# Sheet1.net
KiCad netlist of a schematic drawn in Altium Designer
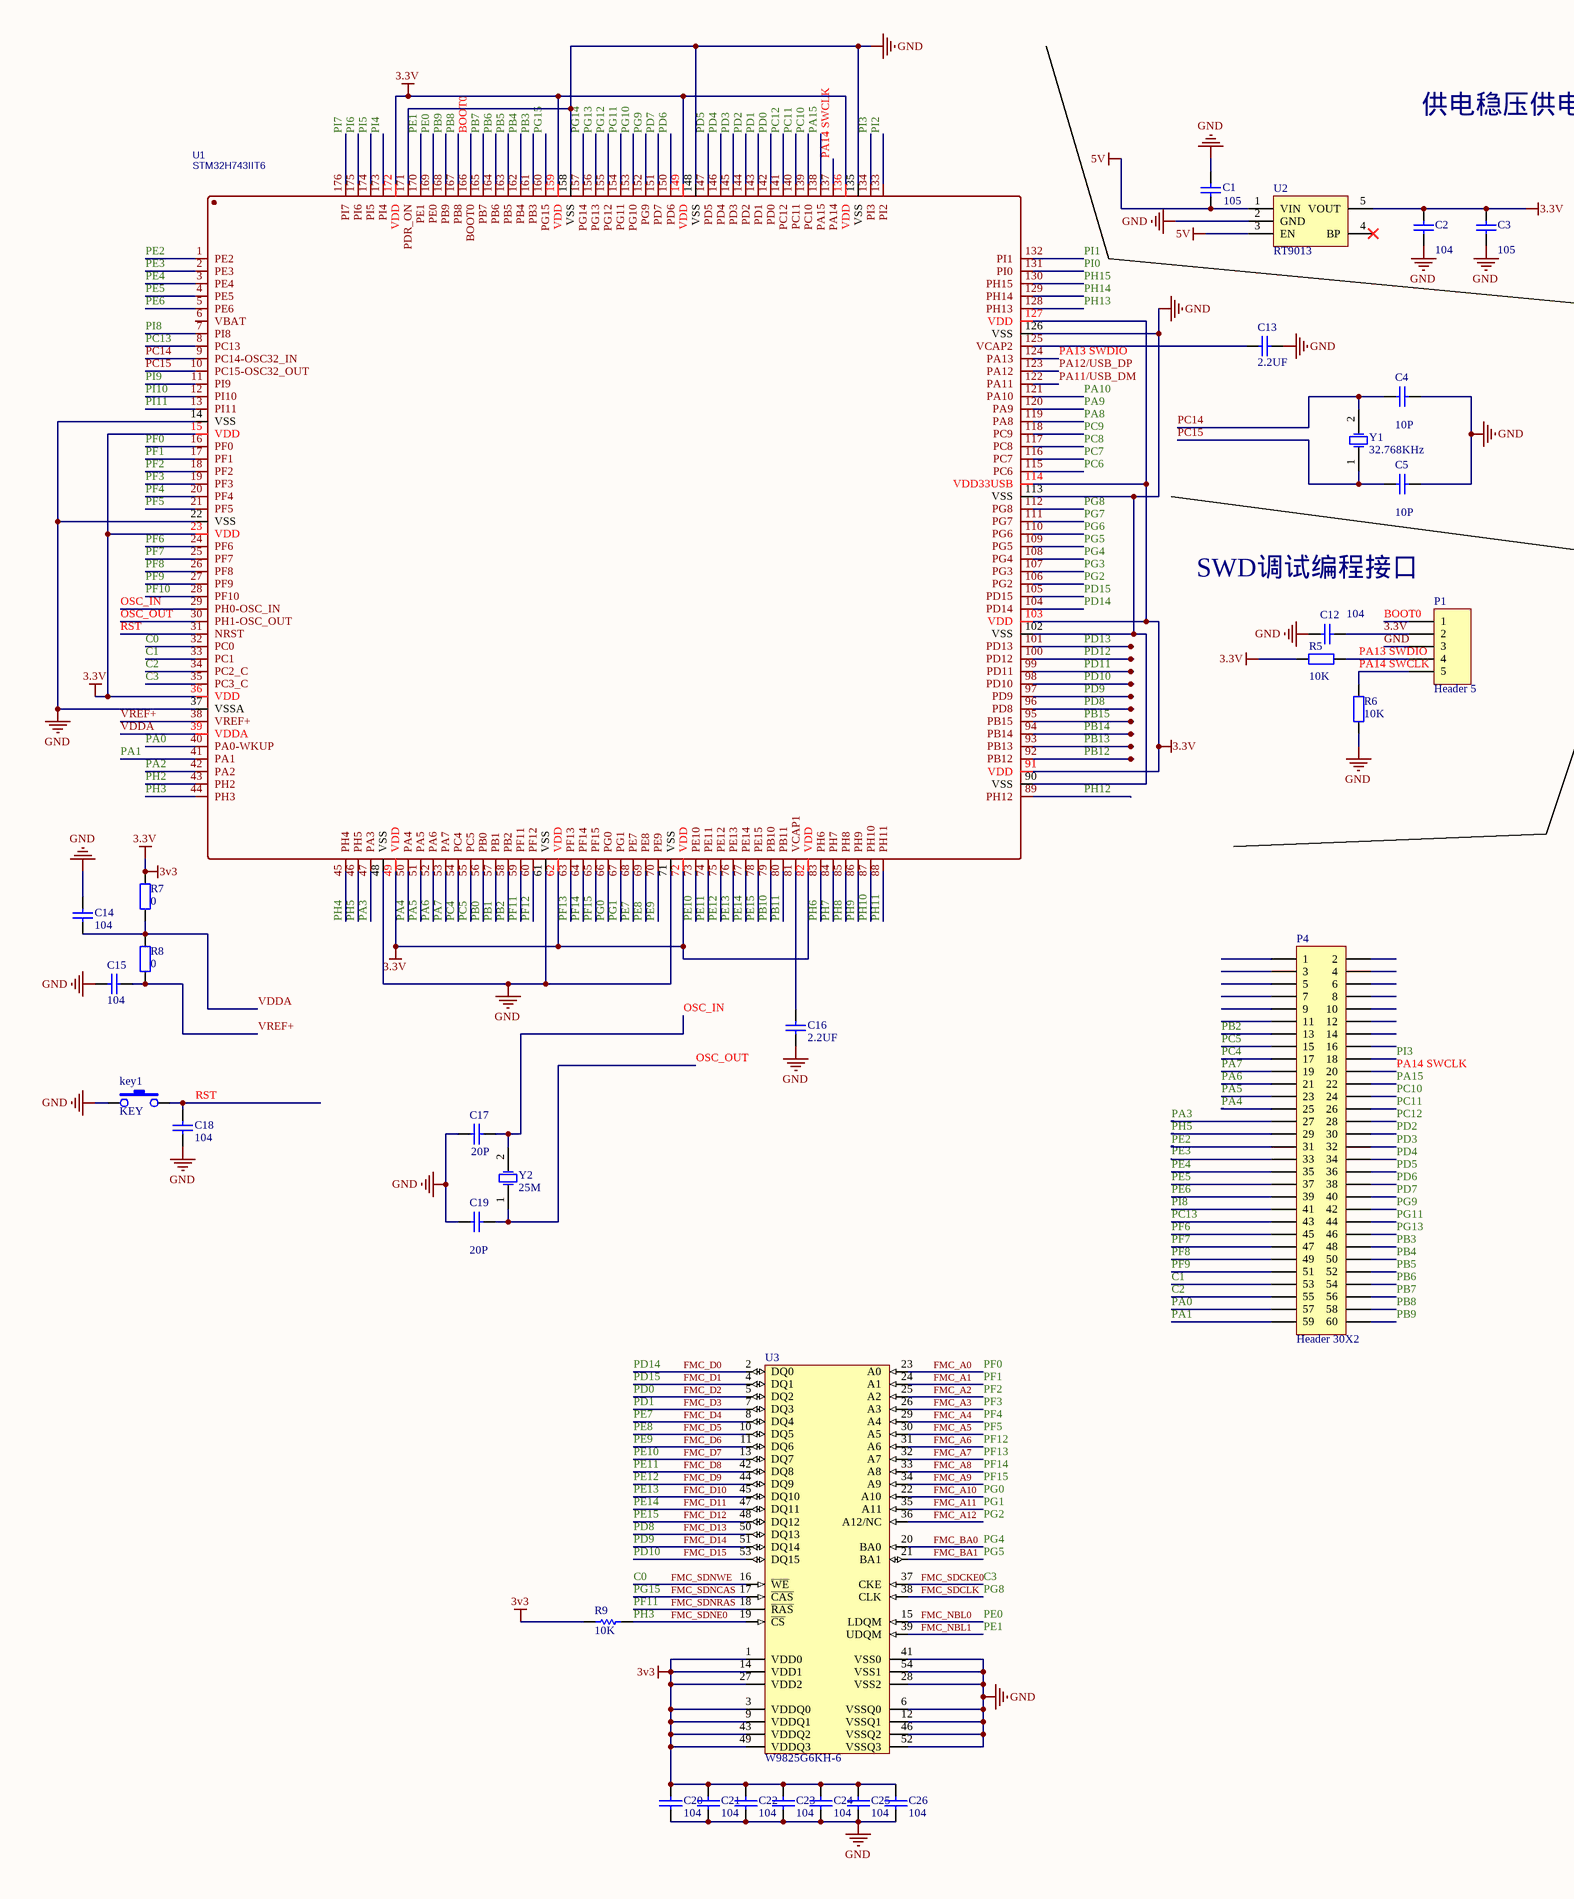
[diagram p0: Sheet1.SchDoc, left]
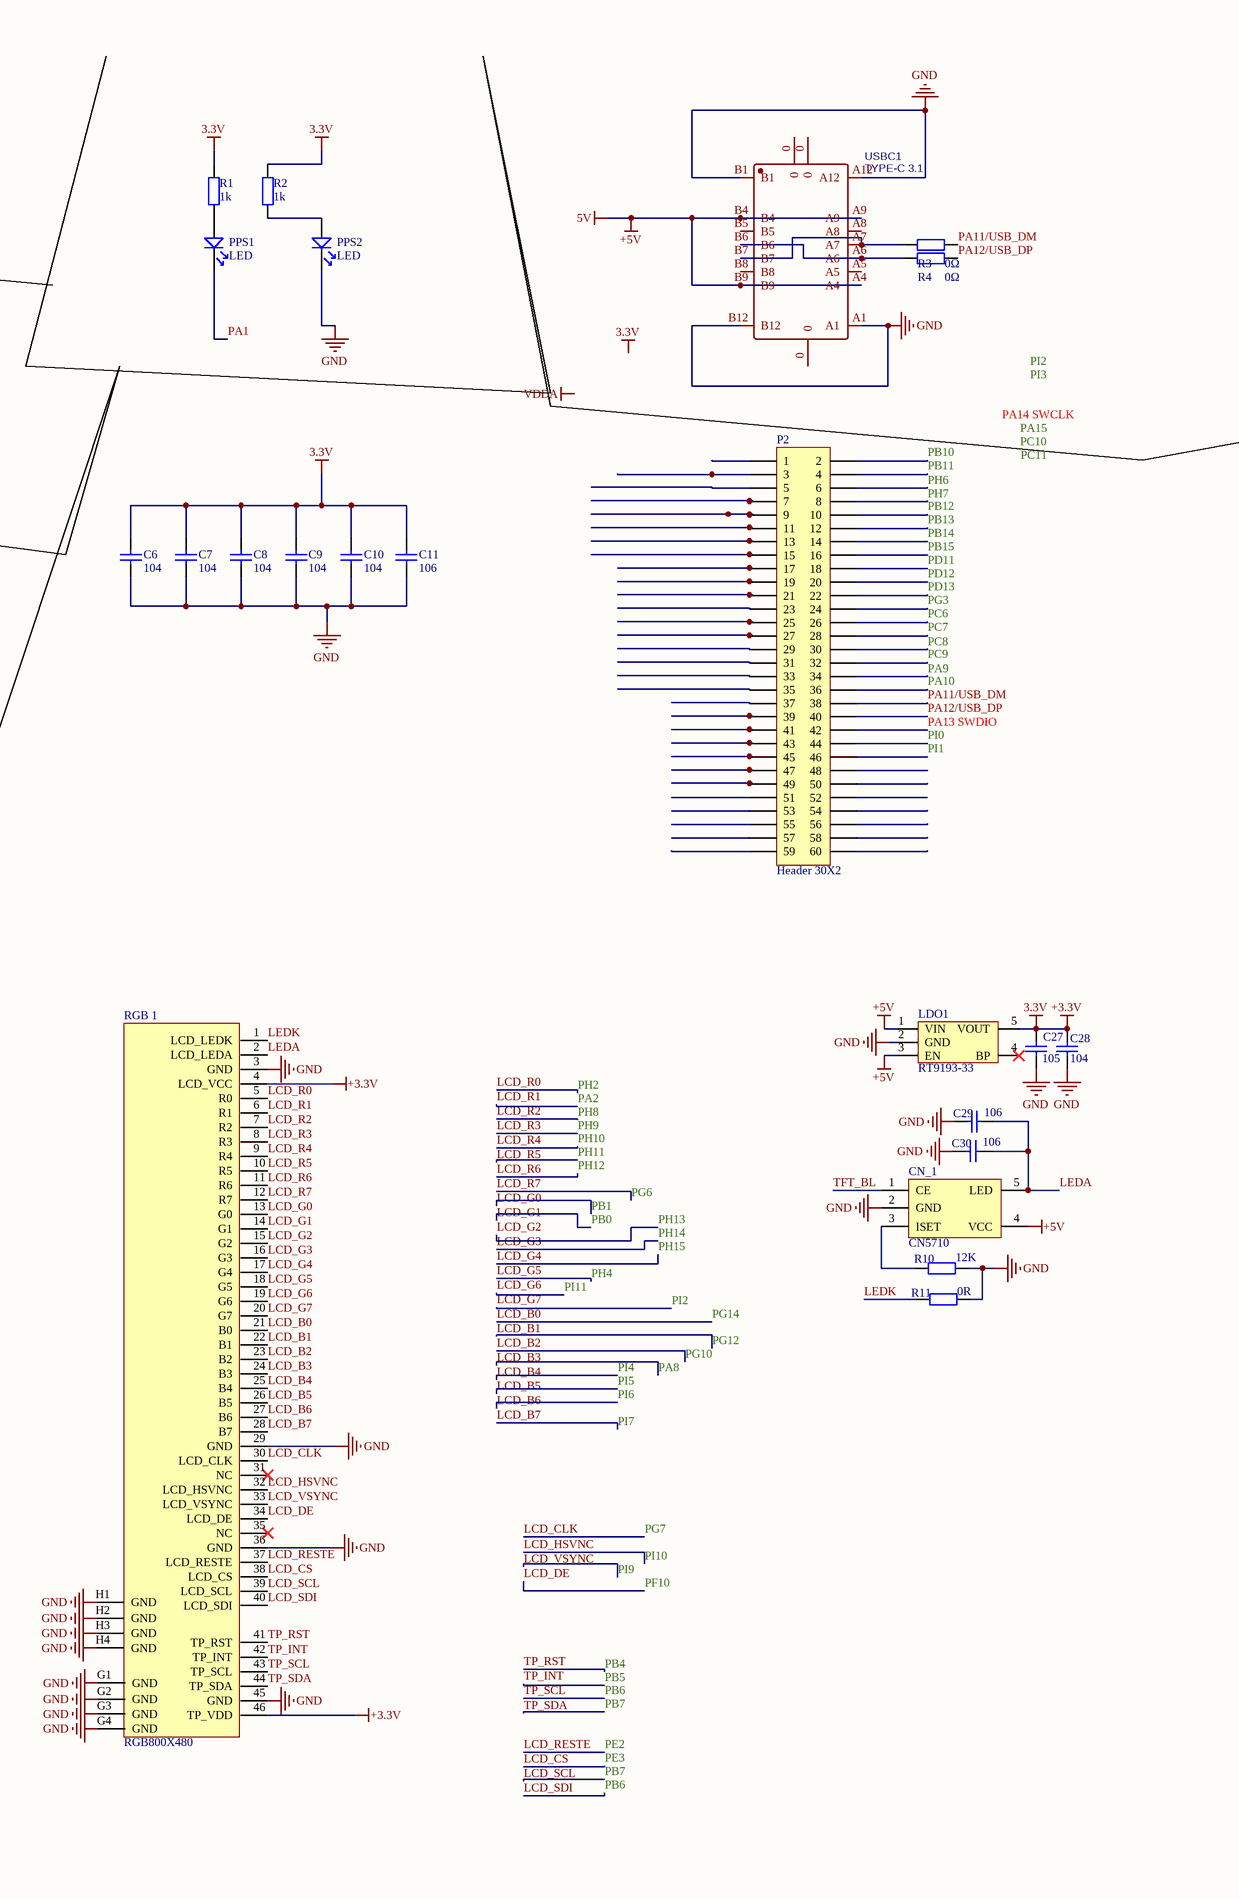
[diagram p1: Sheet1.SchDoc, right]

(export (version "E")
  (design (tool "Eeschema 10.0.6"))
  (components
    (comp (ref "C1")
      (value "105")
      (footprint "0805C")
      (description "Capacitor (Semiconductor SIM Model)")
      (fields (field (name "Comment") "Cap Semi") (field (name "PUBLISHER") "Altium Limited"))
      (libsource (lib "Miscellaneous Devices") (part "Cap Semi"))
    )
    (comp (ref "C2")
      (value "104")
      (footprint "0805C")
      (description "Capacitor (Semiconductor SIM Model)")
      (fields (field (name "Comment") "Cap Semi") (field (name "PUBLISHER") "Altium Limited"))
      (libsource (lib "Miscellaneous Devices") (part "Cap Semi"))
    )
    (comp (ref "C3")
      (value "105")
      (footprint "0805C")
      (description "Capacitor (Semiconductor SIM Model)")
      (fields (field (name "Comment") "Cap Semi") (field (name "PUBLISHER") "Altium Limited"))
      (libsource (lib "Miscellaneous Devices") (part "Cap Semi"))
    )
    (comp (ref "C4")
      (value "10P")
      (footprint "0805C")
      (description "Capacitor")
      (fields (field (name "PUBLISHER") "Altium Limited"))
      (libsource (lib "XH-Library") (part "Cap_1_1"))
    )
    (comp (ref "C5")
      (value "10P")
      (footprint "0805C")
      (description "Capacitor")
      (fields (field (name "PUBLISHER") "Altium Limited"))
      (libsource (lib "XH-Library") (part "Cap_1_1"))
    )
    (comp (ref "C6")
      (value "104")
      (footprint "0805C")
      (description "Capacitor")
      (fields (field (name "PUBLISHER") "Altium Limited"))
      (libsource (lib "XH-Library") (part "Cap_1_1"))
    )
    (comp (ref "C7")
      (value "104")
      (footprint "0805C")
      (description "Capacitor")
      (fields (field (name "PUBLISHER") "Altium Limited"))
      (libsource (lib "XH-Library") (part "Cap_1_1"))
    )
    (comp (ref "C8")
      (value "104")
      (footprint "0805C")
      (description "Capacitor")
      (fields (field (name "PUBLISHER") "Altium Limited"))
      (libsource (lib "XH-Library") (part "Cap_1_1"))
    )
    (comp (ref "C9")
      (value "104")
      (footprint "0805C")
      (description "Capacitor")
      (fields (field (name "PUBLISHER") "Altium Limited"))
      (libsource (lib "XH-Library") (part "Cap_1_1"))
    )
    (comp (ref "C10")
      (value "104")
      (footprint "0805C")
      (description "Capacitor")
      (fields (field (name "PUBLISHER") "Altium Limited"))
      (libsource (lib "XH-Library") (part "Cap_1_1"))
    )
    (comp (ref "C11")
      (value "106")
      (footprint "0805C")
      (description "Capacitor")
      (fields (field (name "PUBLISHER") "Altium Limited"))
      (libsource (lib "XH-Library") (part "Cap_1_1"))
    )
    (comp (ref "C12")
      (value "104")
      (footprint "0805C")
      (fields (field (name "PUBLISHER") "Altium Limited"))
      (libsource (lib "XH-Library") (part "Cap_1_1"))
    )
    (comp (ref "C13")
      (value "2.2UF")
      (footprint "0805C")
      (description "Capacitor")
      (fields (field (name "PUBLISHER") "Altium Limited"))
      (libsource (lib "XH-Library") (part "Cap_1_1"))
    )
    (comp (ref "C14")
      (value "104")
      (footprint "0805C")
      (description "Capacitor")
      (fields (field (name "PUBLISHER") "Altium Limited"))
      (libsource (lib "XH-Library") (part "Cap_1_1"))
    )
    (comp (ref "C15")
      (value "104")
      (footprint "0805C")
      (description "Capacitor")
      (fields (field (name "PUBLISHER") "Altium Limited"))
      (libsource (lib "XH-Library") (part "Cap_1_1"))
    )
    (comp (ref "C16")
      (value "2.2UF")
      (footprint "0805C")
      (description "Capacitor")
      (fields (field (name "PUBLISHER") "Altium Limited"))
      (libsource (lib "XH-Library") (part "Cap_1_1"))
    )
    (comp (ref "C17")
      (value "20P")
      (footprint "0805C")
      (description "Capacitor")
      (fields (field (name "PUBLISHER") "Altium Limited"))
      (libsource (lib "XH-Library") (part "Cap_1_1"))
    )
    (comp (ref "C18")
      (value "104")
      (footprint "0805C")
      (description "Capacitor")
      (fields (field (name "PUBLISHER") "Altium Limited"))
      (libsource (lib "XH-Library") (part "Cap_1_1"))
    )
    (comp (ref "C19")
      (value "20P")
      (footprint "0805C")
      (description "Capacitor")
      (fields (field (name "PUBLISHER") "Altium Limited"))
      (libsource (lib "XH-Library") (part "Cap_1_1"))
    )
    (comp (ref "C20")
      (value "104")
      (footprint "0805C")
      (description "无极性电容")
      (libsource (lib "电容") (part "CAP"))
    )
    (comp (ref "C21")
      (value "104")
      (footprint "0805C")
      (description "无极性电容")
      (libsource (lib "电容") (part "CAP"))
    )
    (comp (ref "C22")
      (value "104")
      (footprint "0805C")
      (description "无极性电容")
      (libsource (lib "电容") (part "CAP"))
    )
    (comp (ref "C23")
      (value "104")
      (footprint "0805C")
      (description "无极性电容")
      (libsource (lib "电容") (part "CAP"))
    )
    (comp (ref "C24")
      (value "104")
      (footprint "0805C")
      (description "无极性电容")
      (libsource (lib "电容") (part "CAP"))
    )
    (comp (ref "C25")
      (value "104")
      (footprint "0805C")
      (description "无极性电容")
      (libsource (lib "电容") (part "CAP"))
    )
    (comp (ref "C26")
      (value "104")
      (footprint "0805C")
      (description "无极性电容")
      (libsource (lib "电容") (part "CAP"))
    )
    (comp (ref "C27")
      (value "105")
      (footprint "0805C")
      (description "Capacitor")
      (fields (field (name "PUBLISHER") "Altium Limited"))
      (libsource (lib "STM32F407VET6mini核心板--原理图库") (part "Cap"))
    )
    (comp (ref "C28")
      (value "104")
      (footprint "0805C")
      (description "Capacitor")
      (fields (field (name "PUBLISHER") "Altium Limited"))
      (libsource (lib "STM32F407VET6mini核心板--原理图库") (part "Cap"))
    )
    (comp (ref "C29")
      (value "106")
      (footprint "0805C")
      (description "Capacitor")
      (fields (field (name "PUBLISHER") "Altium Limited"))
      (libsource (lib "STM32F407VET6mini核心板--原理图库") (part "Cap"))
    )
    (comp (ref "C30")
      (value "106")
      (footprint "0805C")
      (description "Capacitor")
      (fields (field (name "PUBLISHER") "Altium Limited"))
      (libsource (lib "STM32F407VET6mini核心板--原理图库") (part "Cap"))
    )
    (comp (ref "CN_1") (value "CN5710") (footprint "LC-SOT-89-5") (libsource (lib "MINE") (part "CN5710")))
    (comp (ref "key1")
      (value "KEY")
      (footprint "TSW 3*6*4.3-S-W")
      (libsource (lib "XH-Library") (part "KEY"))
    )
    (comp (ref "LDO1")
      (value "RT9193-33")
      (footprint "SOT-23-5")
      (description "3.3V超低压差LDO")
      (libsource (lib "MINE") (part "RT9193-33"))
    )
    (comp (ref "P1")
      (value "Header 5")
      (footprint "HDR2.54-WS-5P")
      (description "Header, 5-Pin")
      (fields (field (name "PUBLISHER") "*"))
      (libsource (lib "XH-Library") (part "Header 5"))
    )
    (comp (ref "P2")
      (value "Header 30X2")
      (footprint "BTB60")
      (description "Header, 30-Pin, Dual row")
      (fields (field (name "PUBLISHER") "Altium Limited"))
      (libsource (lib "XH-Library") (part "Header 30X2"))
    )
    (comp (ref "P4")
      (value "Header 30X2")
      (footprint "BTB60")
      (description "Header, 30-Pin, Dual row")
      (fields (field (name "PUBLISHER") "Altium Limited"))
      (libsource (lib "XH-Library") (part "Header 30X2"))
    )
    (comp (ref "PPS1") (value "LED") (footprint "LED 0805G") (libsource (lib "XH-Library") (part "LED")))
    (comp (ref "PPS2") (value "LED") (footprint "LED 0805G") (libsource (lib "XH-Library") (part "LED")))
    (comp (ref "R1")
      (value "1k")
      (footprint "0805R")
      (description "Resistor")
      (fields (field (name "PUBLISHER") "Altium Limited"))
      (libsource (lib "XH-Library") (part "RES"))
    )
    (comp (ref "R2")
      (value "1k")
      (footprint "0805R")
      (description "Resistor")
      (fields (field (name "PUBLISHER") "Altium Limited"))
      (libsource (lib "XH-Library") (part "RES"))
    )
    (comp (ref "R3")
      (value "0Ω")
      (footprint "0805R")
      (description "Resistor")
      (fields (field (name "PUBLISHER") "Altium Limited"))
      (libsource (lib "") (part "RES_2"))
    )
    (comp (ref "R4")
      (value "0Ω")
      (footprint "0805R")
      (description "Resistor")
      (fields (field (name "PUBLISHER") "Altium Limited"))
      (libsource (lib "") (part "RES_2"))
    )
    (comp (ref "R5")
      (value "10K")
      (footprint "0805R")
      (description "Resistor")
      (fields (field (name "PUBLISHER") "Altium Limited"))
      (libsource (lib "") (part "RES_2"))
    )
    (comp (ref "R6")
      (value "10K")
      (footprint "0805R")
      (description "Resistor")
      (fields (field (name "PUBLISHER") "Altium Limited"))
      (libsource (lib "XH-Library") (part "RES"))
    )
    (comp (ref "R7")
      (value "0")
      (footprint "0805R")
      (description "Resistor")
      (fields (field (name "PUBLISHER") "Altium Limited"))
      (libsource (lib "") (part "RES_1"))
    )
    (comp (ref "R8")
      (value "0")
      (footprint "0805R")
      (description "Resistor")
      (fields (field (name "PUBLISHER") "Altium Limited"))
      (libsource (lib "") (part "RES_1"))
    )
    (comp (ref "R9") (value "10K") (footprint "0805R") (libsource (lib "电阻") (part "RES")))
    (comp (ref "R10")
      (value "12K")
      (footprint "0805R")
      (description "Resistor")
      (fields (field (name "PUBLISHER") "Altium Limited"))
      (libsource (lib "") (part "Res2_1"))
    )
    (comp (ref "R11")
      (value "0R")
      (footprint "0805R")
      (description "Resistor")
      (fields (field (name "PUBLISHER") "Altium Limited"))
      (libsource (lib "STM32F407VET6mini核心板--原理图库") (part "Res2"))
    )
    (comp (ref "RGB 1")
      (value "RGB800X480")
      (footprint "RGB_800x480")
      (libsource (lib "MINE") (part "RGB_800X480"))
    )
    (comp (ref "U1")
      (value "STM32H743IIT6")
      (footprint "LQFP176 24x24_M")
      (fields (field (name "BOM_SUPPLIER PART") "C89597") (field (name "CONTRIBUTOR") "LCSC"))
      (libsource (lib "altium-import") (part "root_0_STM32H743IIT6_"))
    )
    (comp (ref "U2") (value "RT9013") (footprint "SOT23-5") (libsource (lib "Schlib1") (part "RT9013")))
    (comp (ref "U3")
      (value "W9825G6KH-6")
      (footprint "SOP80P1176X120-54N")
      (description "32MB SDRAM")
      (libsource (lib "STM32F429核心板封装库") (part "IS42S16160B"))
    )
    (comp (ref "USBC1")
      (value "TYPE-C 3.1")
      (footprint "TYPE-C-USB-17")
      (libsource (lib "type-c-sch") (part "TYPE-C 3.1"))
    )
    (comp (ref "Y1")
      (value "32.768KHz")
      (footprint "OSC 3215-2P")
      (description "Crystal Oscillator")
      (fields (field (name "PUBLISHER") "Altium Limited"))
      (libsource (lib "XH-Library") (part "XTAL"))
    )
    (comp (ref "Y2")
      (value "25M")
      (footprint "OSC 5032-2P")
      (description "Crystal Oscillator")
      (fields (field (name "PUBLISHER") "Altium Limited"))
      (libsource (lib "XH-Library") (part "XTAL"))
    )
  )
  (nets
    (net (code "1") (name "+3.3V") (class "Default")
      (node (ref "C10") (pin "1") (pinfunction "1_1") (pintype "passive"))
      (node (ref "C11") (pin "1") (pinfunction "1_1") (pintype "passive"))
      (node (ref "C12") (pin "1") (pinfunction "1_1") (pintype "passive"))
      (node (ref "C2") (pin "2") (pinfunction "2_2") (pintype "passive"))
      (node (ref "C20") (pin "2") (pinfunction "2_2") (pintype "passive"))
      (node (ref "C21") (pin "2") (pinfunction "2_2") (pintype "passive"))
      (node (ref "C22") (pin "2") (pinfunction "2_2") (pintype "passive"))
      (node (ref "C23") (pin "2") (pinfunction "2_2") (pintype "passive"))
      (node (ref "C24") (pin "2") (pinfunction "2_2") (pintype "passive"))
      (node (ref "C25") (pin "2") (pinfunction "2_2") (pintype "passive"))
      (node (ref "C26") (pin "2") (pinfunction "2_2") (pintype "passive"))
      (node (ref "C27") (pin "2") (pinfunction "2_2") (pintype "passive"))
      (node (ref "C28") (pin "2") (pinfunction "2_2") (pintype "passive"))
      (node (ref "C3") (pin "2") (pinfunction "2_2") (pintype "passive"))
      (node (ref "C6") (pin "1") (pinfunction "1_1") (pintype "passive"))
      (node (ref "C7") (pin "1") (pinfunction "1_1") (pintype "passive"))
      (node (ref "C8") (pin "1") (pinfunction "1_1") (pintype "passive"))
      (node (ref "C9") (pin "1") (pinfunction "1_1") (pintype "passive"))
      (node (ref "LDO1") (pin "5") (pinfunction "VOUT_5") (pintype "passive"))
      (node (ref "P1") (pin "2") (pinfunction "2_2") (pintype "passive"))
      (node (ref "R1") (pin "2") (pinfunction "2_2") (pintype "passive"))
      (node (ref "R2") (pin "2") (pinfunction "2_2") (pintype "passive"))
      (node (ref "R5") (pin "1") (pinfunction "1_1") (pintype "passive"))
      (node (ref "R7") (pin "1") (pinfunction "1_1") (pintype "passive"))
      (node (ref "R9") (pin "1") (pinfunction "1_1") (pintype "passive"))
      (node (ref "RGB 1") (pin "4") (pinfunction "LCD_VCC_4") (pintype "passive"))
      (node (ref "RGB 1") (pin "46") (pinfunction "TP_VDD_46") (pintype "passive"))
      (node (ref "U1") (pin "103") (pinfunction "VDD_103") (pintype "passive"))
      (node (ref "U1") (pin "114") (pinfunction "VDD33USB_114") (pintype "passive"))
      (node (ref "U1") (pin "127") (pinfunction "VDD_127") (pintype "passive"))
      (node (ref "U1") (pin "136") (pinfunction "VDD_136") (pintype "passive"))
      (node (ref "U1") (pin "149") (pinfunction "VDD_149") (pintype "passive"))
      (node (ref "U1") (pin "15") (pinfunction "VDD_15") (pintype "passive"))
      (node (ref "U1") (pin "159") (pinfunction "VDD_159") (pintype "passive"))
      (node (ref "U1") (pin "172") (pinfunction "VDD_172") (pintype "passive"))
      (node (ref "U1") (pin "23") (pinfunction "VDD_23") (pintype "passive"))
      (node (ref "U1") (pin "36") (pinfunction "VDD_36") (pintype "passive"))
      (node (ref "U1") (pin "49") (pinfunction "VDD_49") (pintype "passive"))
      (node (ref "U1") (pin "62") (pinfunction "VDD_62") (pintype "passive"))
      (node (ref "U1") (pin "72") (pinfunction "VDD_72") (pintype "passive"))
      (node (ref "U1") (pin "82") (pinfunction "VDD_82") (pintype "passive"))
      (node (ref "U1") (pin "91") (pinfunction "VDD_91") (pintype "passive"))
      (node (ref "U2") (pin "5") (pinfunction "VOUT_5") (pintype "passive"))
      (node (ref "U3") (pin "1") (pinfunction "VDD0_1") (pintype "power_in"))
      (node (ref "U3") (pin "14") (pinfunction "VDD1_14") (pintype "power_in"))
      (node (ref "U3") (pin "27") (pinfunction "VDD2_27") (pintype "power_in"))
      (node (ref "U3") (pin "3") (pinfunction "VDDQ0_3") (pintype "power_in"))
      (node (ref "U3") (pin "43") (pinfunction "VDDQ2_43") (pintype "power_in"))
      (node (ref "U3") (pin "49") (pinfunction "VDDQ3_49") (pintype "power_in"))
      (node (ref "U3") (pin "9") (pinfunction "VDDQ1_9") (pintype "power_in"))
    )
    (net (code "2") (name "+5V") (class "Default")
      (node (ref "C1") (pin "1") (pinfunction "1_1") (pintype "passive"))
      (node (ref "CN_1") (pin "4") (pinfunction "VCC_4") (pintype "passive"))
      (node (ref "LDO1") (pin "1") (pinfunction "VIN_1") (pintype "passive"))
      (node (ref "LDO1") (pin "3") (pinfunction "EN_3") (pintype "passive"))
      (node (ref "U2") (pin "1") (pinfunction "VIN_1") (pintype "passive"))
      (node (ref "U2") (pin "3") (pinfunction "EN_3") (pintype "passive"))
      (node (ref "USBC1") (pin "A4") (pinfunction "A4_A4") (pintype "passive"))
      (node (ref "USBC1") (pin "A9") (pinfunction "A9_A9") (pintype "passive"))
      (node (ref "USBC1") (pin "B4") (pinfunction "B4_B4") (pintype "passive"))
      (node (ref "USBC1") (pin "B9") (pinfunction "B9_B9") (pintype "passive"))
    )
    (net (code "3") (name "/BOOT0") (class "Default")
      (node (ref "P1") (pin "1") (pinfunction "1_1") (pintype "passive"))
      (node (ref "U1") (pin "166") (pinfunction "BOOT0_166") (pintype "passive"))
    )
    (net (code "4") (name "/C0") (class "Default")
      (node (ref "U1") (pin "32") (pinfunction "PC0_32") (pintype "passive"))
      (node (ref "U3") (pin "16") (pinfunction "~{WE}_16") (pintype "input"))
    )
    (net (code "5") (name "/C1") (class "Default")
      (node (ref "P4") (pin "53") (pinfunction "53_53") (pintype "passive"))
      (node (ref "U1") (pin "33") (pinfunction "PC1_33") (pintype "passive"))
    )
    (net (code "6") (name "/C2") (class "Default")
      (node (ref "P4") (pin "55") (pinfunction "55_55") (pintype "passive"))
      (node (ref "U1") (pin "34") (pinfunction "PC2_C_34") (pintype "passive"))
    )
    (net (code "7") (name "/C3") (class "Default")
      (node (ref "U1") (pin "35") (pinfunction "PC3_C_35") (pintype "passive"))
      (node (ref "U3") (pin "37") (pinfunction "CKE_37") (pintype "input"))
    )
    (net (code "8") (name "/FMC_A0") (class "Default")
      (node (ref "U1") (pin "16") (pinfunction "PF0_16") (pintype "passive"))
      (node (ref "U3") (pin "23") (pinfunction "A0_23") (pintype "input"))
    )
    (net (code "9") (name "/FMC_A1") (class "Default")
      (node (ref "U1") (pin "17") (pinfunction "PF1_17") (pintype "passive"))
      (node (ref "U3") (pin "24") (pinfunction "A1_24") (pintype "input"))
    )
    (net (code "10") (name "/FMC_A2") (class "Default")
      (node (ref "U1") (pin "18") (pinfunction "PF2_18") (pintype "passive"))
      (node (ref "U3") (pin "25") (pinfunction "A2_25") (pintype "input"))
    )
    (net (code "11") (name "/FMC_A3") (class "Default")
      (node (ref "U1") (pin "19") (pinfunction "PF3_19") (pintype "passive"))
      (node (ref "U3") (pin "26") (pinfunction "A3_26") (pintype "input"))
    )
    (net (code "12") (name "/FMC_A4") (class "Default")
      (node (ref "U1") (pin "20") (pinfunction "PF4_20") (pintype "passive"))
      (node (ref "U3") (pin "29") (pinfunction "A4_29") (pintype "input"))
    )
    (net (code "13") (name "/FMC_A5") (class "Default")
      (node (ref "U1") (pin "21") (pinfunction "PF5_21") (pintype "passive"))
      (node (ref "U3") (pin "30") (pinfunction "A5_30") (pintype "input"))
    )
    (net (code "14") (name "/FMC_A6") (class "Default")
      (node (ref "U1") (pin "60") (pinfunction "PF12_60") (pintype "passive"))
      (node (ref "U3") (pin "31") (pinfunction "A6_31") (pintype "input"))
    )
    (net (code "15") (name "/FMC_A7") (class "Default")
      (node (ref "U1") (pin "63") (pinfunction "PF13_63") (pintype "passive"))
      (node (ref "U3") (pin "32") (pinfunction "A7_32") (pintype "input"))
    )
    (net (code "16") (name "/FMC_A8") (class "Default")
      (node (ref "U1") (pin "64") (pinfunction "PF14_64") (pintype "passive"))
      (node (ref "U3") (pin "33") (pinfunction "A8_33") (pintype "input"))
    )
    (net (code "17") (name "/FMC_A9") (class "Default")
      (node (ref "U1") (pin "65") (pinfunction "PF15_65") (pintype "passive"))
      (node (ref "U3") (pin "34") (pinfunction "A9_34") (pintype "input"))
    )
    (net (code "18") (name "/FMC_A10") (class "Default")
      (node (ref "U1") (pin "66") (pinfunction "PG0_66") (pintype "passive"))
      (node (ref "U3") (pin "22") (pinfunction "A10_22") (pintype "input"))
    )
    (net (code "19") (name "/FMC_A11") (class "Default")
      (node (ref "U1") (pin "67") (pinfunction "PG1_67") (pintype "passive"))
      (node (ref "U3") (pin "35") (pinfunction "A11_35") (pintype "input"))
    )
    (net (code "20") (name "/FMC_A12") (class "Default")
      (node (ref "U1") (pin "106") (pinfunction "PG2_106") (pintype "passive"))
      (node (ref "U3") (pin "36") (pinfunction "A12/NC_36") (pintype "input"))
    )
    (net (code "21") (name "/FMC_BA0") (class "Default")
      (node (ref "U1") (pin "108") (pinfunction "PG4_108") (pintype "passive"))
      (node (ref "U3") (pin "20") (pinfunction "BA0_20") (pintype "input"))
    )
    (net (code "22") (name "/FMC_BA1") (class "Default")
      (node (ref "U1") (pin "109") (pinfunction "PG5_109") (pintype "passive"))
      (node (ref "U3") (pin "21") (pinfunction "BA1_21") (pintype "bidirectional"))
    )
    (net (code "23") (name "/FMC_D0") (class "Default")
      (node (ref "U1") (pin "104") (pinfunction "PD14_104") (pintype "passive"))
      (node (ref "U3") (pin "2") (pinfunction "DQ0_2") (pintype "bidirectional"))
    )
    (net (code "24") (name "/FMC_D1") (class "Default")
      (node (ref "U1") (pin "105") (pinfunction "PD15_105") (pintype "passive"))
      (node (ref "U3") (pin "4") (pinfunction "DQ1_4") (pintype "bidirectional"))
    )
    (net (code "25") (name "/FMC_D2") (class "Default")
      (node (ref "U1") (pin "142") (pinfunction "PD0_142") (pintype "passive"))
      (node (ref "U3") (pin "5") (pinfunction "DQ2_5") (pintype "bidirectional"))
    )
    (net (code "26") (name "/FMC_D3") (class "Default")
      (node (ref "U1") (pin "143") (pinfunction "PD1_143") (pintype "passive"))
      (node (ref "U3") (pin "7") (pinfunction "DQ3_7") (pintype "bidirectional"))
    )
    (net (code "27") (name "/FMC_D4") (class "Default")
      (node (ref "U1") (pin "68") (pinfunction "PE7_68") (pintype "passive"))
      (node (ref "U3") (pin "8") (pinfunction "DQ4_8") (pintype "bidirectional"))
    )
    (net (code "28") (name "/FMC_D5") (class "Default")
      (node (ref "U1") (pin "69") (pinfunction "PE8_69") (pintype "passive"))
      (node (ref "U3") (pin "10") (pinfunction "DQ5_10") (pintype "bidirectional"))
    )
    (net (code "29") (name "/FMC_D6") (class "Default")
      (node (ref "U1") (pin "70") (pinfunction "PE9_70") (pintype "passive"))
      (node (ref "U3") (pin "11") (pinfunction "DQ6_11") (pintype "bidirectional"))
    )
    (net (code "30") (name "/FMC_D7") (class "Default")
      (node (ref "U1") (pin "73") (pinfunction "PE10_73") (pintype "passive"))
      (node (ref "U3") (pin "13") (pinfunction "DQ7_13") (pintype "bidirectional"))
    )
    (net (code "31") (name "/FMC_D8") (class "Default")
      (node (ref "U1") (pin "74") (pinfunction "PE11_74") (pintype "passive"))
      (node (ref "U3") (pin "42") (pinfunction "DQ8_42") (pintype "bidirectional"))
    )
    (net (code "32") (name "/FMC_D9") (class "Default")
      (node (ref "U1") (pin "75") (pinfunction "PE12_75") (pintype "passive"))
      (node (ref "U3") (pin "44") (pinfunction "DQ9_44") (pintype "bidirectional"))
    )
    (net (code "33") (name "/FMC_D10") (class "Default")
      (node (ref "U1") (pin "76") (pinfunction "PE13_76") (pintype "passive"))
      (node (ref "U3") (pin "45") (pinfunction "DQ10_45") (pintype "bidirectional"))
    )
    (net (code "34") (name "/FMC_D11") (class "Default")
      (node (ref "U1") (pin "77") (pinfunction "PE14_77") (pintype "passive"))
      (node (ref "U3") (pin "47") (pinfunction "DQ11_47") (pintype "bidirectional"))
    )
    (net (code "35") (name "/FMC_D12") (class "Default")
      (node (ref "U1") (pin "78") (pinfunction "PE15_78") (pintype "passive"))
      (node (ref "U3") (pin "48") (pinfunction "DQ12_48") (pintype "bidirectional"))
    )
    (net (code "36") (name "/FMC_D13") (class "Default")
      (node (ref "U1") (pin "96") (pinfunction "PD8_96") (pintype "passive"))
      (node (ref "U3") (pin "50") (pinfunction "DQ13_50") (pintype "bidirectional"))
    )
    (net (code "37") (name "/FMC_D14") (class "Default")
      (node (ref "U1") (pin "97") (pinfunction "PD9_97") (pintype "passive"))
      (node (ref "U3") (pin "51") (pinfunction "DQ14_51") (pintype "bidirectional"))
    )
    (net (code "38") (name "/FMC_D15") (class "Default")
      (node (ref "U1") (pin "98") (pinfunction "PD10_98") (pintype "passive"))
      (node (ref "U3") (pin "53") (pinfunction "DQ15_53") (pintype "bidirectional"))
    )
    (net (code "39") (name "/FMC_NBL0") (class "Default")
      (node (ref "U1") (pin "169") (pinfunction "PE0_169") (pintype "passive"))
      (node (ref "U3") (pin "15") (pinfunction "LDQM_15") (pintype "input"))
    )
    (net (code "40") (name "/FMC_NBL1") (class "Default")
      (node (ref "U1") (pin "170") (pinfunction "PE1_170") (pintype "passive"))
      (node (ref "U3") (pin "39") (pinfunction "UDQM_39") (pintype "input"))
    )
    (net (code "41") (name "/FMC_SDCLK") (class "Default")
      (node (ref "U1") (pin "112") (pinfunction "PG8_112") (pintype "passive"))
      (node (ref "U3") (pin "38") (pinfunction "CLK_38") (pintype "input"))
    )
    (net (code "42") (name "/FMC_SDNCAS") (class "Default")
      (node (ref "U1") (pin "160") (pinfunction "PG15_160") (pintype "passive"))
      (node (ref "U3") (pin "17") (pinfunction "~{CAS}_17") (pintype "input"))
    )
    (net (code "43") (name "/FMC_SDNE0") (class "Default")
      (node (ref "R9") (pin "2") (pinfunction "2_2") (pintype "passive"))
      (node (ref "U1") (pin "44") (pinfunction "PH3_44") (pintype "passive"))
      (node (ref "U3") (pin "19") (pinfunction "~{CS}_19") (pintype "input"))
    )
    (net (code "44") (name "/FMC_SDNRAS") (class "Default")
      (node (ref "U1") (pin "59") (pinfunction "PF11_59") (pintype "passive"))
      (node (ref "U3") (pin "18") (pinfunction "~{RAS}_18") (pintype "passive"))
    )
    (net (code "45") (name "/LCD_B0") (class "Default")
      (node (ref "RGB 1") (pin "21") (pinfunction "B0_21") (pintype "passive"))
      (node (ref "U1") (pin "157") (pinfunction "PG14_157") (pintype "passive"))
    )
    (net (code "46") (name "/LCD_B1") (class "Default")
      (node (ref "RGB 1") (pin "22") (pinfunction "B1_22") (pintype "passive"))
      (node (ref "U1") (pin "155") (pinfunction "PG12_155") (pintype "passive"))
    )
    (net (code "47") (name "/LCD_B2") (class "Default")
      (node (ref "RGB 1") (pin "23") (pinfunction "B2_23") (pintype "passive"))
      (node (ref "U1") (pin "153") (pinfunction "PG10_153") (pintype "passive"))
    )
    (net (code "48") (name "/LCD_B3") (class "Default")
      (node (ref "RGB 1") (pin "24") (pinfunction "B3_24") (pintype "passive"))
      (node (ref "U1") (pin "119") (pinfunction "PA8_119") (pintype "passive"))
    )
    (net (code "49") (name "/LCD_B4") (class "Default")
      (node (ref "RGB 1") (pin "25") (pinfunction "B4_25") (pintype "passive"))
      (node (ref "U1") (pin "173") (pinfunction "PI4_173") (pintype "passive"))
    )
    (net (code "50") (name "/LCD_B5") (class "Default")
      (node (ref "RGB 1") (pin "26") (pinfunction "B5_26") (pintype "passive"))
      (node (ref "U1") (pin "174") (pinfunction "PI5_174") (pintype "passive"))
    )
    (net (code "51") (name "/LCD_B6") (class "Default")
      (node (ref "RGB 1") (pin "27") (pinfunction "B6_27") (pintype "passive"))
      (node (ref "U1") (pin "175") (pinfunction "PI6_175") (pintype "passive"))
    )
    (net (code "52") (name "/LCD_B7") (class "Default")
      (node (ref "RGB 1") (pin "28") (pinfunction "B7_28") (pintype "passive"))
      (node (ref "U1") (pin "176") (pinfunction "PI7_176") (pintype "passive"))
    )
    (net (code "53") (name "/LCD_CLK") (class "Default")
      (node (ref "RGB 1") (pin "30") (pinfunction "LCD_CLK_30") (pintype "passive"))
      (node (ref "U1") (pin "111") (pinfunction "PG7_111") (pintype "passive"))
    )
    (net (code "54") (name "/LCD_CS") (class "Default")
      (node (ref "P4") (pin "33") (pinfunction "33_33") (pintype "passive"))
      (node (ref "RGB 1") (pin "38") (pinfunction "LCD_CS_38") (pintype "passive"))
      (node (ref "U1") (pin "2") (pinfunction "PE3_2") (pintype "passive"))
    )
    (net (code "55") (name "/LCD_DE") (class "Default")
      (node (ref "RGB 1") (pin "34") (pinfunction "LCD_DE_34") (pintype "passive"))
      (node (ref "U1") (pin "28") (pinfunction "PF10_28") (pintype "passive"))
    )
    (net (code "56") (name "/LCD_G0") (class "Default")
      (node (ref "RGB 1") (pin "13") (pinfunction "G0_13") (pintype "passive"))
      (node (ref "U1") (pin "57") (pinfunction "PB1_57") (pintype "passive"))
    )
    (net (code "57") (name "/LCD_G1") (class "Default")
      (node (ref "RGB 1") (pin "14") (pinfunction "G1_14") (pintype "passive"))
      (node (ref "U1") (pin "56") (pinfunction "PB0_56") (pintype "passive"))
    )
    (net (code "58") (name "/LCD_G2") (class "Default")
      (node (ref "RGB 1") (pin "15") (pinfunction "G2_15") (pintype "passive"))
      (node (ref "U1") (pin "128") (pinfunction "PH13_128") (pintype "passive"))
    )
    (net (code "59") (name "/LCD_G3") (class "Default")
      (node (ref "RGB 1") (pin "16") (pinfunction "G3_16") (pintype "passive"))
      (node (ref "U1") (pin "129") (pinfunction "PH14_129") (pintype "passive"))
    )
    (net (code "60") (name "/LCD_G4") (class "Default")
      (node (ref "RGB 1") (pin "17") (pinfunction "G4_17") (pintype "passive"))
      (node (ref "U1") (pin "130") (pinfunction "PH15_130") (pintype "passive"))
    )
    (net (code "61") (name "/LCD_G5") (class "Default")
      (node (ref "RGB 1") (pin "18") (pinfunction "G5_18") (pintype "passive"))
      (node (ref "U1") (pin "45") (pinfunction "PH4_45") (pintype "passive"))
    )
    (net (code "62") (name "/LCD_G6") (class "Default")
      (node (ref "RGB 1") (pin "19") (pinfunction "G6_19") (pintype "passive"))
      (node (ref "U1") (pin "13") (pinfunction "PI11_13") (pintype "passive"))
    )
    (net (code "63") (name "/LCD_G7") (class "Default")
      (node (ref "RGB 1") (pin "20") (pinfunction "G7_20") (pintype "passive"))
      (node (ref "U1") (pin "133") (pinfunction "PI2_133") (pintype "passive"))
    )
    (net (code "64") (name "/LCD_HSVNC") (class "Default")
      (node (ref "RGB 1") (pin "32") (pinfunction "LCD_HSVNC_32") (pintype "passive"))
      (node (ref "U1") (pin "12") (pinfunction "PI10_12") (pintype "passive"))
    )
    (net (code "65") (name "/LCD_R0") (class "Default")
      (node (ref "RGB 1") (pin "5") (pinfunction "R0_5") (pintype "passive"))
      (node (ref "U1") (pin "43") (pinfunction "PH2_43") (pintype "passive"))
    )
    (net (code "66") (name "/LCD_R1") (class "Default")
      (node (ref "RGB 1") (pin "6") (pinfunction "R1_6") (pintype "passive"))
      (node (ref "U1") (pin "42") (pinfunction "PA2_42") (pintype "passive"))
    )
    (net (code "67") (name "/LCD_R2") (class "Default")
      (node (ref "RGB 1") (pin "7") (pinfunction "R2_7") (pintype "passive"))
      (node (ref "U1") (pin "85") (pinfunction "PH8_85") (pintype "passive"))
    )
    (net (code "68") (name "/LCD_R3") (class "Default")
      (node (ref "RGB 1") (pin "8") (pinfunction "R3_8") (pintype "passive"))
      (node (ref "U1") (pin "86") (pinfunction "PH9_86") (pintype "passive"))
    )
    (net (code "69") (name "/LCD_R4") (class "Default")
      (node (ref "RGB 1") (pin "9") (pinfunction "R4_9") (pintype "passive"))
      (node (ref "U1") (pin "87") (pinfunction "PH10_87") (pintype "passive"))
    )
    (net (code "70") (name "/LCD_R5") (class "Default")
      (node (ref "RGB 1") (pin "10") (pinfunction "R5_10") (pintype "passive"))
      (node (ref "U1") (pin "88") (pinfunction "PH11_88") (pintype "passive"))
    )
    (net (code "71") (name "/LCD_R6") (class "Default")
      (node (ref "RGB 1") (pin "11") (pinfunction "R6_11") (pintype "passive"))
      (node (ref "U1") (pin "89") (pinfunction "PH12_89") (pintype "passive"))
    )
    (net (code "72") (name "/LCD_R7") (class "Default")
      (node (ref "RGB 1") (pin "12") (pinfunction "R7_12") (pintype "passive"))
      (node (ref "U1") (pin "110") (pinfunction "PG6_110") (pintype "passive"))
    )
    (net (code "73") (name "/LCD_RESTE") (class "Default")
      (node (ref "P4") (pin "31") (pinfunction "31_31") (pintype "passive"))
      (node (ref "RGB 1") (pin "37") (pinfunction "LCD_RESTE_37") (pintype "passive"))
      (node (ref "U1") (pin "1") (pinfunction "PE2_1") (pintype "passive"))
    )
    (net (code "74") (name "/LCD_SCL") (class "Default")
      (node (ref "P4") (pin "56") (pinfunction "56_56") (pintype "passive"))
      (node (ref "RGB 1") (pin "39") (pinfunction "LCD_SCL_39") (pintype "passive"))
      (node (ref "RGB 1") (pin "44") (pinfunction "TP_SDA_44") (pintype "passive"))
      (node (ref "U1") (pin "165") (pinfunction "PB7_165") (pintype "passive"))
    )
    (net (code "75") (name "/LCD_SDI") (class "Default")
      (node (ref "P4") (pin "54") (pinfunction "54_54") (pintype "passive"))
      (node (ref "RGB 1") (pin "40") (pinfunction "LCD_SDI_40") (pintype "passive"))
      (node (ref "RGB 1") (pin "43") (pinfunction "TP_SCL_43") (pintype "passive"))
      (node (ref "U1") (pin "164") (pinfunction "PB6_164") (pintype "passive"))
    )
    (net (code "76") (name "/LCD_VSYNC") (class "Default")
      (node (ref "RGB 1") (pin "33") (pinfunction "LCD_VSYNC_33") (pintype "passive"))
      (node (ref "U1") (pin "11") (pinfunction "PI9_11") (pintype "passive"))
    )
    (net (code "77") (name "/LEDA") (class "Default")
      (node (ref "C29") (pin "1") (pinfunction "1_1") (pintype "passive"))
      (node (ref "C30") (pin "1") (pinfunction "1_1") (pintype "passive"))
      (node (ref "CN_1") (pin "5") (pinfunction "LED_5") (pintype "passive"))
      (node (ref "RGB 1") (pin "2") (pinfunction "LCD_LEDA_2") (pintype "passive"))
    )
    (net (code "78") (name "/LEDK") (class "Default")
      (node (ref "R11") (pin "1") (pinfunction "1_1") (pintype "passive"))
      (node (ref "RGB 1") (pin "1") (pinfunction "LCD_LEDK_1") (pintype "passive"))
    )
    (net (code "79") (name "/OSC_IN") (class "Default")
      (node (ref "C17") (pin "1") (pinfunction "1_1") (pintype "passive"))
      (node (ref "U1") (pin "29") (pinfunction "PH0-OSC_IN_29") (pintype "passive"))
      (node (ref "Y2") (pin "2") (pinfunction "OSC2_2") (pintype "passive"))
    )
    (net (code "80") (name "/OSC_OUT") (class "Default")
      (node (ref "C19") (pin "1") (pinfunction "1_1") (pintype "passive"))
      (node (ref "U1") (pin "30") (pinfunction "PH1-OSC_OUT_30") (pintype "passive"))
      (node (ref "Y2") (pin "1") (pinfunction "OSC1_1") (pintype "passive"))
    )
    (net (code "81") (name "/PA0") (class "Default")
      (node (ref "P4") (pin "57") (pinfunction "57_57") (pintype "passive"))
      (node (ref "U1") (pin "40") (pinfunction "PA0-WKUP_40") (pintype "passive"))
    )
    (net (code "82") (name "/PA1") (class "Default")
      (node (ref "P4") (pin "59") (pinfunction "59_59") (pintype "passive"))
      (node (ref "PPS1") (pin "2") (pinfunction "2_2") (pintype "passive"))
      (node (ref "U1") (pin "41") (pinfunction "PA1_41") (pintype "passive"))
    )
    (net (code "83") (name "/PA3") (class "Default")
      (node (ref "P4") (pin "27") (pinfunction "27_27") (pintype "passive"))
      (node (ref "U1") (pin "47") (pinfunction "PA3_47") (pintype "passive"))
    )
    (net (code "84") (name "/PA4") (class "Default")
      (node (ref "P4") (pin "25") (pinfunction "25_25") (pintype "passive"))
      (node (ref "U1") (pin "50") (pinfunction "PA4_50") (pintype "passive"))
    )
    (net (code "85") (name "/PA5") (class "Default")
      (node (ref "P4") (pin "23") (pinfunction "23_23") (pintype "passive"))
      (node (ref "U1") (pin "51") (pinfunction "PA5_51") (pintype "passive"))
    )
    (net (code "86") (name "/PA6") (class "Default")
      (node (ref "P4") (pin "21") (pinfunction "21_21") (pintype "passive"))
      (node (ref "U1") (pin "52") (pinfunction "PA6_52") (pintype "passive"))
    )
    (net (code "87") (name "/PA7") (class "Default")
      (node (ref "P4") (pin "19") (pinfunction "19_19") (pintype "passive"))
      (node (ref "U1") (pin "53") (pinfunction "PA7_53") (pintype "passive"))
    )
    (net (code "88") (name "/PA9") (class "Default")
      (node (ref "P2") (pin "34") (pinfunction "34_34") (pintype "passive"))
      (node (ref "U1") (pin "120") (pinfunction "PA9_120") (pintype "passive"))
    )
    (net (code "89") (name "/PA10") (class "Default")
      (node (ref "P2") (pin "36") (pinfunction "36_36") (pintype "passive"))
      (node (ref "U1") (pin "121") (pinfunction "PA10_121") (pintype "passive"))
    )
    (net (code "90") (name "/PA11{slash}USB_DM") (class "Default")
      (node (ref "P2") (pin "38") (pinfunction "38_38") (pintype "passive"))
      (node (ref "R3") (pin "2") (pinfunction "2_2") (pintype "passive"))
      (node (ref "U1") (pin "122") (pinfunction "PA11_122") (pintype "passive"))
    )
    (net (code "91") (name "/PA12{slash}USB_DP") (class "Default")
      (node (ref "P2") (pin "40") (pinfunction "40_40") (pintype "passive"))
      (node (ref "R4") (pin "2") (pinfunction "2_2") (pintype "passive"))
      (node (ref "U1") (pin "123") (pinfunction "PA12_123") (pintype "passive"))
    )
    (net (code "92") (name "/PA13 SWDIO") (class "Default")
      (node (ref "P1") (pin "4") (pinfunction "4_4") (pintype "passive"))
      (node (ref "P2") (pin "42") (pinfunction "42_42") (pintype "passive"))
      (node (ref "R5") (pin "2") (pinfunction "2_2") (pintype "passive"))
      (node (ref "U1") (pin "124") (pinfunction "PA13_124") (pintype "passive"))
    )
    (net (code "93") (name "/PA14 SWCLK") (class "Default")
      (node (ref "P1") (pin "5") (pinfunction "5_5") (pintype "passive"))
      (node (ref "P4") (pin "20") (pinfunction "20_20") (pintype "passive"))
      (node (ref "R6") (pin "2") (pinfunction "2_2") (pintype "passive"))
      (node (ref "U1") (pin "137") (pinfunction "PA14_137") (pintype "passive"))
    )
    (net (code "94") (name "/PA15") (class "Default")
      (node (ref "P4") (pin "22") (pinfunction "22_22") (pintype "passive"))
      (node (ref "U1") (pin "138") (pinfunction "PA15_138") (pintype "passive"))
    )
    (net (code "95") (name "/PB2") (class "Default")
      (node (ref "P4") (pin "13") (pinfunction "13_13") (pintype "passive"))
      (node (ref "U1") (pin "58") (pinfunction "PB2_58") (pintype "passive"))
    )
    (net (code "96") (name "/PB3") (class "Default")
      (node (ref "P4") (pin "48") (pinfunction "48_48") (pintype "passive"))
      (node (ref "U1") (pin "161") (pinfunction "PB3_161") (pintype "passive"))
    )
    (net (code "97") (name "/PB4") (class "Default")
      (node (ref "P4") (pin "50") (pinfunction "50_50") (pintype "passive"))
      (node (ref "RGB 1") (pin "41") (pinfunction "TP_RST_41") (pintype "passive"))
      (node (ref "U1") (pin "162") (pinfunction "PB4_162") (pintype "passive"))
    )
    (net (code "98") (name "/PB5") (class "Default")
      (node (ref "P4") (pin "52") (pinfunction "52_52") (pintype "passive"))
      (node (ref "RGB 1") (pin "42") (pinfunction "TP_INT_42") (pintype "passive"))
      (node (ref "U1") (pin "163") (pinfunction "PB5_163") (pintype "passive"))
    )
    (net (code "99") (name "/PB8") (class "Default")
      (node (ref "P4") (pin "58") (pinfunction "58_58") (pintype "passive"))
      (node (ref "U1") (pin "167") (pinfunction "PB8_167") (pintype "passive"))
    )
    (net (code "100") (name "/PB9") (class "Default")
      (node (ref "P4") (pin "60") (pinfunction "60_60") (pintype "passive"))
      (node (ref "U1") (pin "168") (pinfunction "PB9_168") (pintype "passive"))
    )
    (net (code "101") (name "/PB10") (class "Default")
      (node (ref "P2") (pin "2") (pinfunction "2_2") (pintype "passive"))
      (node (ref "U1") (pin "79") (pinfunction "PB10_79") (pintype "passive"))
    )
    (net (code "102") (name "/PB11") (class "Default")
      (node (ref "P2") (pin "4") (pinfunction "4_4") (pintype "passive"))
      (node (ref "U1") (pin "80") (pinfunction "PB11_80") (pintype "passive"))
    )
    (net (code "103") (name "/PB12") (class "Default")
      (node (ref "P2") (pin "10") (pinfunction "10_10") (pintype "passive"))
      (node (ref "U1") (pin "92") (pinfunction "PB12_92") (pintype "passive"))
    )
    (net (code "104") (name "/PB13") (class "Default")
      (node (ref "P2") (pin "12") (pinfunction "12_12") (pintype "passive"))
      (node (ref "U1") (pin "93") (pinfunction "PB13_93") (pintype "passive"))
    )
    (net (code "105") (name "/PB14") (class "Default")
      (node (ref "P2") (pin "14") (pinfunction "14_14") (pintype "passive"))
      (node (ref "U1") (pin "94") (pinfunction "PB14_94") (pintype "passive"))
    )
    (net (code "106") (name "/PB15") (class "Default")
      (node (ref "P2") (pin "16") (pinfunction "16_16") (pintype "passive"))
      (node (ref "U1") (pin "95") (pinfunction "PB15_95") (pintype "passive"))
    )
    (net (code "107") (name "/PC4") (class "Default")
      (node (ref "P4") (pin "17") (pinfunction "17_17") (pintype "passive"))
      (node (ref "U1") (pin "54") (pinfunction "PC4_54") (pintype "passive"))
    )
    (net (code "108") (name "/PC5") (class "Default")
      (node (ref "P4") (pin "15") (pinfunction "15_15") (pintype "passive"))
      (node (ref "U1") (pin "55") (pinfunction "PC5_55") (pintype "passive"))
    )
    (net (code "109") (name "/PC6") (class "Default")
      (node (ref "P2") (pin "26") (pinfunction "26_26") (pintype "passive"))
      (node (ref "U1") (pin "115") (pinfunction "PC6_115") (pintype "passive"))
    )
    (net (code "110") (name "/PC7") (class "Default")
      (node (ref "P2") (pin "28") (pinfunction "28_28") (pintype "passive"))
      (node (ref "U1") (pin "116") (pinfunction "PC7_116") (pintype "passive"))
    )
    (net (code "111") (name "/PC8") (class "Default")
      (node (ref "P2") (pin "30") (pinfunction "30_30") (pintype "passive"))
      (node (ref "U1") (pin "117") (pinfunction "PC8_117") (pintype "passive"))
    )
    (net (code "112") (name "/PC9") (class "Default")
      (node (ref "P2") (pin "32") (pinfunction "32_32") (pintype "passive"))
      (node (ref "U1") (pin "118") (pinfunction "PC9_118") (pintype "passive"))
    )
    (net (code "113") (name "/PC10") (class "Default")
      (node (ref "P4") (pin "24") (pinfunction "24_24") (pintype "passive"))
      (node (ref "U1") (pin "139") (pinfunction "PC10_139") (pintype "passive"))
    )
    (net (code "114") (name "/PC11") (class "Default")
      (node (ref "P4") (pin "26") (pinfunction "26_26") (pintype "passive"))
      (node (ref "U1") (pin "140") (pinfunction "PC11_140") (pintype "passive"))
    )
    (net (code "115") (name "/PC12") (class "Default")
      (node (ref "P4") (pin "28") (pinfunction "28_28") (pintype "passive"))
      (node (ref "U1") (pin "141") (pinfunction "PC12_141") (pintype "passive"))
    )
    (net (code "116") (name "/PC13") (class "Default")
      (node (ref "P4") (pin "43") (pinfunction "43_43") (pintype "passive"))
      (node (ref "U1") (pin "8") (pinfunction "PC13_8") (pintype "passive"))
    )
    (net (code "117") (name "/PC14") (class "Default")
      (node (ref "C4") (pin "2") (pinfunction "2_2") (pintype "passive"))
      (node (ref "U1") (pin "9") (pinfunction "PC14-OSC32_IN_9") (pintype "passive"))
      (node (ref "Y1") (pin "2") (pinfunction "OSC2_2") (pintype "passive"))
    )
    (net (code "118") (name "/PC15") (class "Default")
      (node (ref "C5") (pin "2") (pinfunction "2_2") (pintype "passive"))
      (node (ref "U1") (pin "10") (pinfunction "PC15-OSC32_OUT_10") (pintype "passive"))
      (node (ref "Y1") (pin "1") (pinfunction "OSC1_1") (pintype "passive"))
    )
    (net (code "119") (name "/PD2") (class "Default")
      (node (ref "P4") (pin "30") (pinfunction "30_30") (pintype "passive"))
      (node (ref "U1") (pin "144") (pinfunction "PD2_144") (pintype "passive"))
    )
    (net (code "120") (name "/PD3") (class "Default")
      (node (ref "P4") (pin "32") (pinfunction "32_32") (pintype "passive"))
      (node (ref "U1") (pin "145") (pinfunction "PD3_145") (pintype "passive"))
    )
    (net (code "121") (name "/PD4") (class "Default")
      (node (ref "P4") (pin "34") (pinfunction "34_34") (pintype "passive"))
      (node (ref "U1") (pin "146") (pinfunction "PD4_146") (pintype "passive"))
    )
    (net (code "122") (name "/PD5") (class "Default")
      (node (ref "P4") (pin "36") (pinfunction "36_36") (pintype "passive"))
      (node (ref "U1") (pin "147") (pinfunction "PD5_147") (pintype "passive"))
    )
    (net (code "123") (name "/PD6") (class "Default")
      (node (ref "P4") (pin "38") (pinfunction "38_38") (pintype "passive"))
      (node (ref "U1") (pin "150") (pinfunction "PD6_150") (pintype "passive"))
    )
    (net (code "124") (name "/PD7") (class "Default")
      (node (ref "P4") (pin "40") (pinfunction "40_40") (pintype "passive"))
      (node (ref "U1") (pin "151") (pinfunction "PD7_151") (pintype "passive"))
    )
    (net (code "125") (name "/PD11") (class "Default")
      (node (ref "P2") (pin "18") (pinfunction "18_18") (pintype "passive"))
      (node (ref "U1") (pin "99") (pinfunction "PD11_99") (pintype "passive"))
    )
    (net (code "126") (name "/PD12") (class "Default")
      (node (ref "P2") (pin "20") (pinfunction "20_20") (pintype "passive"))
      (node (ref "U1") (pin "100") (pinfunction "PD12_100") (pintype "passive"))
    )
    (net (code "127") (name "/PD13") (class "Default")
      (node (ref "P2") (pin "22") (pinfunction "22_22") (pintype "passive"))
      (node (ref "U1") (pin "101") (pinfunction "PD13_101") (pintype "passive"))
    )
    (net (code "128") (name "/PE4") (class "Default")
      (node (ref "P4") (pin "35") (pinfunction "35_35") (pintype "passive"))
      (node (ref "U1") (pin "3") (pinfunction "PE4_3") (pintype "passive"))
    )
    (net (code "129") (name "/PE5") (class "Default")
      (node (ref "P4") (pin "37") (pinfunction "37_37") (pintype "passive"))
      (node (ref "U1") (pin "4") (pinfunction "PE5_4") (pintype "passive"))
    )
    (net (code "130") (name "/PE6") (class "Default")
      (node (ref "P4") (pin "39") (pinfunction "39_39") (pintype "passive"))
      (node (ref "U1") (pin "5") (pinfunction "PE6_5") (pintype "passive"))
    )
    (net (code "131") (name "/PF6") (class "Default")
      (node (ref "P4") (pin "45") (pinfunction "45_45") (pintype "passive"))
      (node (ref "U1") (pin "24") (pinfunction "PF6_24") (pintype "passive"))
    )
    (net (code "132") (name "/PF7") (class "Default")
      (node (ref "P4") (pin "47") (pinfunction "47_47") (pintype "passive"))
      (node (ref "U1") (pin "25") (pinfunction "PF7_25") (pintype "passive"))
    )
    (net (code "133") (name "/PF8") (class "Default")
      (node (ref "P4") (pin "49") (pinfunction "49_49") (pintype "passive"))
      (node (ref "U1") (pin "26") (pinfunction "PF8_26") (pintype "passive"))
    )
    (net (code "134") (name "/PF9") (class "Default")
      (node (ref "P4") (pin "51") (pinfunction "51_51") (pintype "passive"))
      (node (ref "U1") (pin "27") (pinfunction "PF9_27") (pintype "passive"))
    )
    (net (code "135") (name "/PG3") (class "Default")
      (node (ref "P2") (pin "24") (pinfunction "24_24") (pintype "passive"))
      (node (ref "U1") (pin "107") (pinfunction "PG3_107") (pintype "passive"))
    )
    (net (code "136") (name "/PG9") (class "Default")
      (node (ref "P4") (pin "42") (pinfunction "42_42") (pintype "passive"))
      (node (ref "U1") (pin "152") (pinfunction "PG9_152") (pintype "passive"))
    )
    (net (code "137") (name "/PG11") (class "Default")
      (node (ref "P4") (pin "44") (pinfunction "44_44") (pintype "passive"))
      (node (ref "U1") (pin "154") (pinfunction "PG11_154") (pintype "passive"))
    )
    (net (code "138") (name "/PG13") (class "Default")
      (node (ref "P4") (pin "46") (pinfunction "46_46") (pintype "passive"))
      (node (ref "U1") (pin "156") (pinfunction "PG13_156") (pintype "passive"))
    )
    (net (code "139") (name "/PH5") (class "Default")
      (node (ref "P4") (pin "29") (pinfunction "29_29") (pintype "passive"))
      (node (ref "U1") (pin "46") (pinfunction "PH5_46") (pintype "passive"))
    )
    (net (code "140") (name "/PH6") (class "Default")
      (node (ref "P2") (pin "6") (pinfunction "6_6") (pintype "passive"))
      (node (ref "U1") (pin "83") (pinfunction "PH6_83") (pintype "passive"))
    )
    (net (code "141") (name "/PH7") (class "Default")
      (node (ref "P2") (pin "8") (pinfunction "8_8") (pintype "passive"))
      (node (ref "U1") (pin "84") (pinfunction "PH7_84") (pintype "passive"))
    )
    (net (code "142") (name "/PI0") (class "Default")
      (node (ref "P2") (pin "44") (pinfunction "44_44") (pintype "passive"))
      (node (ref "U1") (pin "131") (pinfunction "PI0_131") (pintype "passive"))
    )
    (net (code "143") (name "/PI1") (class "Default")
      (node (ref "P2") (pin "46") (pinfunction "46_46") (pintype "passive"))
      (node (ref "U1") (pin "132") (pinfunction "PI1_132") (pintype "passive"))
    )
    (net (code "144") (name "/PI3") (class "Default")
      (node (ref "P4") (pin "18") (pinfunction "18_18") (pintype "passive"))
      (node (ref "U1") (pin "134") (pinfunction "PI3_134") (pintype "passive"))
    )
    (net (code "145") (name "/PI8") (class "Default")
      (node (ref "P4") (pin "41") (pinfunction "41_41") (pintype "passive"))
      (node (ref "U1") (pin "7") (pinfunction "PI8_7") (pintype "passive"))
    )
    (net (code "146") (name "/RST") (class "Default")
      (node (ref "C18") (pin "2") (pinfunction "2_2") (pintype "passive"))
      (node (ref "U1") (pin "31") (pinfunction "NRST_31") (pintype "passive"))
      (node (ref "key1") (pin "2") (pinfunction "2_2") (pintype "passive"))
    )
    (net (code "147") (name "/TFT_BL") (class "Default")
      (node (ref "CN_1") (pin "1") (pinfunction "CE_1") (pintype "passive"))
    )
    (net (code "148") (name "/VREF+") (class "Default")
      (node (ref "C15") (pin "1") (pinfunction "1_1") (pintype "passive"))
      (node (ref "R8") (pin "2") (pinfunction "2_2") (pintype "passive"))
      (node (ref "U1") (pin "38") (pinfunction "VREF+_38") (pintype "passive"))
    )
    (net (code "149") (name "GND") (class "Default")
      (node (ref "C1") (pin "2") (pinfunction "2_2") (pintype "passive"))
      (node (ref "C10") (pin "2") (pinfunction "2_2") (pintype "passive"))
      (node (ref "C11") (pin "2") (pinfunction "2_2") (pintype "passive"))
      (node (ref "C12") (pin "2") (pinfunction "2_2") (pintype "passive"))
      (node (ref "C13") (pin "2") (pinfunction "2_2") (pintype "passive"))
      (node (ref "C14") (pin "1") (pinfunction "1_1") (pintype "passive"))
      (node (ref "C15") (pin "2") (pinfunction "2_2") (pintype "passive"))
      (node (ref "C16") (pin "2") (pinfunction "2_2") (pintype "passive"))
      (node (ref "C17") (pin "2") (pinfunction "2_2") (pintype "passive"))
      (node (ref "C18") (pin "1") (pinfunction "1_1") (pintype "passive"))
      (node (ref "C19") (pin "2") (pinfunction "2_2") (pintype "passive"))
      (node (ref "C2") (pin "1") (pinfunction "1_1") (pintype "passive"))
      (node (ref "C20") (pin "1") (pinfunction "1_1") (pintype "passive"))
      (node (ref "C21") (pin "1") (pinfunction "1_1") (pintype "passive"))
      (node (ref "C22") (pin "1") (pinfunction "1_1") (pintype "passive"))
      (node (ref "C23") (pin "1") (pinfunction "1_1") (pintype "passive"))
      (node (ref "C24") (pin "1") (pinfunction "1_1") (pintype "passive"))
      (node (ref "C25") (pin "1") (pinfunction "1_1") (pintype "passive"))
      (node (ref "C26") (pin "1") (pinfunction "1_1") (pintype "passive"))
      (node (ref "C27") (pin "1") (pinfunction "1_1") (pintype "passive"))
      (node (ref "C28") (pin "1") (pinfunction "1_1") (pintype "passive"))
      (node (ref "C29") (pin "2") (pinfunction "2_2") (pintype "passive"))
      (node (ref "C3") (pin "1") (pinfunction "1_1") (pintype "passive"))
      (node (ref "C30") (pin "2") (pinfunction "2_2") (pintype "passive"))
      (node (ref "C4") (pin "1") (pinfunction "1_1") (pintype "passive"))
      (node (ref "C5") (pin "1") (pinfunction "1_1") (pintype "passive"))
      (node (ref "C6") (pin "2") (pinfunction "2_2") (pintype "passive"))
      (node (ref "C7") (pin "2") (pinfunction "2_2") (pintype "passive"))
      (node (ref "C8") (pin "2") (pinfunction "2_2") (pintype "passive"))
      (node (ref "C9") (pin "2") (pinfunction "2_2") (pintype "passive"))
      (node (ref "CN_1") (pin "2") (pinfunction "GND_2") (pintype "passive"))
      (node (ref "LDO1") (pin "2") (pinfunction "GND_2") (pintype "passive"))
      (node (ref "P1") (pin "3") (pinfunction "3_3") (pintype "passive"))
      (node (ref "PPS2") (pin "2") (pinfunction "2_2") (pintype "passive"))
      (node (ref "R10") (pin "1") (pinfunction "1_1") (pintype "passive"))
      (node (ref "R11") (pin "2") (pinfunction "2_2") (pintype "passive"))
      (node (ref "R6") (pin "1") (pinfunction "1_1") (pintype "passive"))
      (node (ref "RGB 1") (pin "29") (pinfunction "GND_29") (pintype "passive"))
      (node (ref "RGB 1") (pin "3") (pinfunction "GND_3") (pintype "passive"))
      (node (ref "RGB 1") (pin "36") (pinfunction "GND_36") (pintype "passive"))
      (node (ref "RGB 1") (pin "45") (pinfunction "GND_45") (pintype "passive"))
      (node (ref "RGB 1") (pin "G1") (pinfunction "GND_G1") (pintype "passive"))
      (node (ref "RGB 1") (pin "G2") (pinfunction "GND_G2") (pintype "passive"))
      (node (ref "RGB 1") (pin "G3") (pinfunction "GND_G3") (pintype "passive"))
      (node (ref "RGB 1") (pin "G4") (pinfunction "GND_G4") (pintype "passive"))
      (node (ref "RGB 1") (pin "H1") (pinfunction "GND_H1") (pintype "passive"))
      (node (ref "RGB 1") (pin "H2") (pinfunction "GND_H2") (pintype "passive"))
      (node (ref "RGB 1") (pin "H3") (pinfunction "GND_H3") (pintype "passive"))
      (node (ref "RGB 1") (pin "H4") (pinfunction "GND_H4") (pintype "passive"))
      (node (ref "U1") (pin "102") (pinfunction "VSS_102") (pintype "passive"))
      (node (ref "U1") (pin "113") (pinfunction "VSS_113") (pintype "passive"))
      (node (ref "U1") (pin "126") (pinfunction "VSS_126") (pintype "passive"))
      (node (ref "U1") (pin "135") (pinfunction "VSS_135") (pintype "passive"))
      (node (ref "U1") (pin "14") (pinfunction "VSS_14") (pintype "passive"))
      (node (ref "U1") (pin "148") (pinfunction "VSS_148") (pintype "passive"))
      (node (ref "U1") (pin "158") (pinfunction "VSS_158") (pintype "passive"))
      (node (ref "U1") (pin "171") (pinfunction "PDR_ON_171") (pintype "passive"))
      (node (ref "U1") (pin "22") (pinfunction "VSS_22") (pintype "passive"))
      (node (ref "U1") (pin "37") (pinfunction "VSSA_37") (pintype "passive"))
      (node (ref "U1") (pin "48") (pinfunction "VSS_48") (pintype "passive"))
      (node (ref "U1") (pin "61") (pinfunction "VSS_61") (pintype "passive"))
      (node (ref "U1") (pin "71") (pinfunction "VSS_71") (pintype "passive"))
      (node (ref "U1") (pin "90") (pinfunction "VSS_90") (pintype "passive"))
      (node (ref "U2") (pin "2") (pinfunction "GND_2") (pintype "passive"))
      (node (ref "U3") (pin "12") (pinfunction "VSSQ1_12") (pintype "power_in"))
      (node (ref "U3") (pin "28") (pinfunction "VSS2_28") (pintype "power_in"))
      (node (ref "U3") (pin "41") (pinfunction "VSS0_41") (pintype "power_in"))
      (node (ref "U3") (pin "46") (pinfunction "VSSQ2_46") (pintype "power_in"))
      (node (ref "U3") (pin "52") (pinfunction "VSSQ3_52") (pintype "power_in"))
      (node (ref "U3") (pin "54") (pinfunction "VSS1_54") (pintype "power_in"))
      (node (ref "U3") (pin "6") (pinfunction "VSSQ0_6") (pintype "power_in"))
      (node (ref "USBC1") (pin "A1") (pinfunction "A1_A1") (pintype "passive"))
      (node (ref "USBC1") (pin "A12") (pinfunction "A12_A12") (pintype "passive"))
      (node (ref "USBC1") (pin "B1") (pinfunction "B1_B1") (pintype "passive"))
      (node (ref "USBC1") (pin "B12") (pinfunction "B12_B12") (pintype "passive"))
      (node (ref "key1") (pin "1") (pinfunction "1_1") (pintype "passive"))
    )
    (net (code "150") (name "Net-(CN_1-ISET)") (class "Default")
      (node (ref "CN_1") (pin "3") (pinfunction "ISET_3") (pintype "passive"))
      (node (ref "R10") (pin "2") (pinfunction "2_2") (pintype "passive"))
    )
    (net (code "151") (name "Net-(PPS1-Pad1)") (class "Default")
      (node (ref "PPS1") (pin "1") (pinfunction "1_1") (pintype "passive"))
      (node (ref "R1") (pin "1") (pinfunction "1_1") (pintype "passive"))
    )
    (net (code "152") (name "Net-(PPS2-Pad1)") (class "Default")
      (node (ref "PPS2") (pin "1") (pinfunction "1_1") (pintype "passive"))
      (node (ref "R2") (pin "1") (pinfunction "1_1") (pintype "passive"))
    )
    (net (code "153") (name "Net-(R3-Pad1)") (class "Default")
      (node (ref "R3") (pin "1") (pinfunction "1_1") (pintype "passive"))
      (node (ref "USBC1") (pin "A7") (pinfunction "A7_A7") (pintype "passive"))
      (node (ref "USBC1") (pin "B7") (pinfunction "B7_B7") (pintype "passive"))
    )
    (net (code "154") (name "Net-(R4-Pad1)") (class "Default")
      (node (ref "R4") (pin "1") (pinfunction "1_1") (pintype "passive"))
      (node (ref "USBC1") (pin "A6") (pinfunction "A6_A6") (pintype "passive"))
      (node (ref "USBC1") (pin "B6") (pinfunction "B6_B6") (pintype "passive"))
    )
    (net (code "155") (name "Net-(U1-VCAP1)") (class "Default")
      (node (ref "C16") (pin "1") (pinfunction "1_1") (pintype "passive"))
      (node (ref "U1") (pin "81") (pinfunction "VCAP1_81") (pintype "passive"))
    )
    (net (code "156") (name "Net-(U1-VCAP2)") (class "Default")
      (node (ref "C13") (pin "1") (pinfunction "1_1") (pintype "passive"))
      (node (ref "U1") (pin "125") (pinfunction "VCAP2_125") (pintype "passive"))
    )
    (net (code "157") (name "VDDA") (class "Default")
      (node (ref "C14") (pin "2") (pinfunction "2_2") (pintype "passive"))
      (node (ref "R7") (pin "2") (pinfunction "2_2") (pintype "passive"))
      (node (ref "R8") (pin "1") (pinfunction "1_1") (pintype "passive"))
      (node (ref "U1") (pin "39") (pinfunction "VDDA_39") (pintype "passive"))
    )
    (net (code "158") (name "unconnected-(LDO1-BP-Pad4)") (class "Default")
      (node (ref "LDO1") (pin "4") (pinfunction "BP_4") (pintype "passive+no_connect"))
    )
    (net (code "159") (name "unconnected-(P2-Pad1)") (class "Default")
      (node (ref "P2") (pin "1") (pinfunction "1_1") (pintype "passive"))
    )
    (net (code "160") (name "unconnected-(P2-Pad3)") (class "Default")
      (node (ref "P2") (pin "3") (pinfunction "3_3") (pintype "passive"))
    )
    (net (code "161") (name "unconnected-(P2-Pad5)") (class "Default")
      (node (ref "P2") (pin "5") (pinfunction "5_5") (pintype "passive"))
    )
    (net (code "162") (name "unconnected-(P2-Pad7)") (class "Default")
      (node (ref "P2") (pin "7") (pinfunction "7_7") (pintype "passive"))
    )
    (net (code "163") (name "unconnected-(P2-Pad9)") (class "Default")
      (node (ref "P2") (pin "9") (pinfunction "9_9") (pintype "passive"))
    )
    (net (code "164") (name "unconnected-(P2-Pad11)") (class "Default")
      (node (ref "P2") (pin "11") (pinfunction "11_11") (pintype "passive"))
    )
    (net (code "165") (name "unconnected-(P2-Pad13)") (class "Default")
      (node (ref "P2") (pin "13") (pinfunction "13_13") (pintype "passive"))
    )
    (net (code "166") (name "unconnected-(P2-Pad15)") (class "Default")
      (node (ref "P2") (pin "15") (pinfunction "15_15") (pintype "passive"))
    )
    (net (code "167") (name "unconnected-(P2-Pad17)") (class "Default")
      (node (ref "P2") (pin "17") (pinfunction "17_17") (pintype "passive"))
    )
    (net (code "168") (name "unconnected-(P2-Pad19)") (class "Default")
      (node (ref "P2") (pin "19") (pinfunction "19_19") (pintype "passive"))
    )
    (net (code "169") (name "unconnected-(P2-Pad21)") (class "Default")
      (node (ref "P2") (pin "21") (pinfunction "21_21") (pintype "passive"))
    )
    (net (code "170") (name "unconnected-(P2-Pad23)") (class "Default")
      (node (ref "P2") (pin "23") (pinfunction "23_23") (pintype "passive"))
    )
    (net (code "171") (name "unconnected-(P2-Pad25)") (class "Default")
      (node (ref "P2") (pin "25") (pinfunction "25_25") (pintype "passive"))
    )
    (net (code "172") (name "unconnected-(P2-Pad27)") (class "Default")
      (node (ref "P2") (pin "27") (pinfunction "27_27") (pintype "passive"))
    )
    (net (code "173") (name "unconnected-(P2-Pad29)") (class "Default")
      (node (ref "P2") (pin "29") (pinfunction "29_29") (pintype "passive"))
    )
    (net (code "174") (name "unconnected-(P2-Pad31)") (class "Default")
      (node (ref "P2") (pin "31") (pinfunction "31_31") (pintype "passive"))
    )
    (net (code "175") (name "unconnected-(P2-Pad33)") (class "Default")
      (node (ref "P2") (pin "33") (pinfunction "33_33") (pintype "passive"))
    )
    (net (code "176") (name "unconnected-(P2-Pad35)") (class "Default")
      (node (ref "P2") (pin "35") (pinfunction "35_35") (pintype "passive"))
    )
    (net (code "177") (name "unconnected-(P2-Pad37)") (class "Default")
      (node (ref "P2") (pin "37") (pinfunction "37_37") (pintype "passive"))
    )
    (net (code "178") (name "unconnected-(P2-Pad39)") (class "Default")
      (node (ref "P2") (pin "39") (pinfunction "39_39") (pintype "passive"))
    )
    (net (code "179") (name "unconnected-(P2-Pad41)") (class "Default")
      (node (ref "P2") (pin "41") (pinfunction "41_41") (pintype "passive"))
    )
    (net (code "180") (name "unconnected-(P2-Pad43)") (class "Default")
      (node (ref "P2") (pin "43") (pinfunction "43_43") (pintype "passive"))
    )
    (net (code "181") (name "unconnected-(P2-Pad45)") (class "Default")
      (node (ref "P2") (pin "45") (pinfunction "45_45") (pintype "passive"))
    )
    (net (code "182") (name "unconnected-(P2-Pad47)") (class "Default")
      (node (ref "P2") (pin "47") (pinfunction "47_47") (pintype "passive"))
    )
    (net (code "183") (name "unconnected-(P2-Pad48)") (class "Default")
      (node (ref "P2") (pin "48") (pinfunction "48_48") (pintype "passive"))
    )
    (net (code "184") (name "unconnected-(P2-Pad49)") (class "Default")
      (node (ref "P2") (pin "49") (pinfunction "49_49") (pintype "passive"))
    )
    (net (code "185") (name "unconnected-(P2-Pad50)") (class "Default")
      (node (ref "P2") (pin "50") (pinfunction "50_50") (pintype "passive"))
    )
    (net (code "186") (name "unconnected-(P2-Pad51)") (class "Default")
      (node (ref "P2") (pin "51") (pinfunction "51_51") (pintype "passive"))
    )
    (net (code "187") (name "unconnected-(P2-Pad52)") (class "Default")
      (node (ref "P2") (pin "52") (pinfunction "52_52") (pintype "passive"))
    )
    (net (code "188") (name "unconnected-(P2-Pad53)") (class "Default")
      (node (ref "P2") (pin "53") (pinfunction "53_53") (pintype "passive"))
    )
    (net (code "189") (name "unconnected-(P2-Pad54)") (class "Default")
      (node (ref "P2") (pin "54") (pinfunction "54_54") (pintype "passive"))
    )
    (net (code "190") (name "unconnected-(P2-Pad55)") (class "Default")
      (node (ref "P2") (pin "55") (pinfunction "55_55") (pintype "passive"))
    )
    (net (code "191") (name "unconnected-(P2-Pad56)") (class "Default")
      (node (ref "P2") (pin "56") (pinfunction "56_56") (pintype "passive"))
    )
    (net (code "192") (name "unconnected-(P2-Pad57)") (class "Default")
      (node (ref "P2") (pin "57") (pinfunction "57_57") (pintype "passive"))
    )
    (net (code "193") (name "unconnected-(P2-Pad58)") (class "Default")
      (node (ref "P2") (pin "58") (pinfunction "58_58") (pintype "passive"))
    )
    (net (code "194") (name "unconnected-(P2-Pad59)") (class "Default")
      (node (ref "P2") (pin "59") (pinfunction "59_59") (pintype "passive"))
    )
    (net (code "195") (name "unconnected-(P2-Pad60)") (class "Default")
      (node (ref "P2") (pin "60") (pinfunction "60_60") (pintype "passive"))
    )
    (net (code "196") (name "unconnected-(P4-Pad1)") (class "Default")
      (node (ref "P4") (pin "1") (pinfunction "1_1") (pintype "passive"))
    )
    (net (code "197") (name "unconnected-(P4-Pad2)") (class "Default")
      (node (ref "P4") (pin "2") (pinfunction "2_2") (pintype "passive"))
    )
    (net (code "198") (name "unconnected-(P4-Pad3)") (class "Default")
      (node (ref "P4") (pin "3") (pinfunction "3_3") (pintype "passive"))
    )
    (net (code "199") (name "unconnected-(P4-Pad4)") (class "Default")
      (node (ref "P4") (pin "4") (pinfunction "4_4") (pintype "passive"))
    )
    (net (code "200") (name "unconnected-(P4-Pad5)") (class "Default")
      (node (ref "P4") (pin "5") (pinfunction "5_5") (pintype "passive"))
    )
    (net (code "201") (name "unconnected-(P4-Pad6)") (class "Default")
      (node (ref "P4") (pin "6") (pinfunction "6_6") (pintype "passive"))
    )
    (net (code "202") (name "unconnected-(P4-Pad7)") (class "Default")
      (node (ref "P4") (pin "7") (pinfunction "7_7") (pintype "passive"))
    )
    (net (code "203") (name "unconnected-(P4-Pad8)") (class "Default")
      (node (ref "P4") (pin "8") (pinfunction "8_8") (pintype "passive"))
    )
    (net (code "204") (name "unconnected-(P4-Pad9)") (class "Default")
      (node (ref "P4") (pin "9") (pinfunction "9_9") (pintype "passive"))
    )
    (net (code "205") (name "unconnected-(P4-Pad10)") (class "Default")
      (node (ref "P4") (pin "10") (pinfunction "10_10") (pintype "passive"))
    )
    (net (code "206") (name "unconnected-(P4-Pad11)") (class "Default")
      (node (ref "P4") (pin "11") (pinfunction "11_11") (pintype "passive"))
    )
    (net (code "207") (name "unconnected-(P4-Pad12)") (class "Default")
      (node (ref "P4") (pin "12") (pinfunction "12_12") (pintype "passive"))
    )
    (net (code "208") (name "unconnected-(P4-Pad14)") (class "Default")
      (node (ref "P4") (pin "14") (pinfunction "14_14") (pintype "passive"))
    )
    (net (code "209") (name "unconnected-(P4-Pad16)") (class "Default")
      (node (ref "P4") (pin "16") (pinfunction "16_16") (pintype "passive"))
    )
    (net (code "210") (name "unconnected-(RGB 1-NC-Pad31)") (class "Default")
      (node (ref "RGB 1") (pin "31") (pinfunction "NC_31") (pintype "passive+no_connect"))
    )
    (net (code "211") (name "unconnected-(RGB 1-NC-Pad35)") (class "Default")
      (node (ref "RGB 1") (pin "35") (pinfunction "NC_35") (pintype "passive+no_connect"))
    )
    (net (code "212") (name "unconnected-(U1-VBAT-Pad6)") (class "Default")
      (node (ref "U1") (pin "6") (pinfunction "VBAT_6") (pintype "passive"))
    )
    (net (code "213") (name "unconnected-(U2-BP-Pad4)") (class "Default")
      (node (ref "U2") (pin "4") (pinfunction "BP_4") (pintype "passive+no_connect"))
    )
    (net (code "214") (name "unconnected-(USBC1-Pad0)") (class "Default")
      (node (ref "USBC1") (pin "0") (pinfunction "0_0") (pintype "passive"))
    )
    (net (code "215") (name "unconnected-(USBC1-Pad0)_1") (class "Default")
      (node (ref "USBC1") (pin "0") (pinfunction "0_0") (pintype "passive"))
    )
    (net (code "216") (name "unconnected-(USBC1-Pad0)_2") (class "Default")
      (node (ref "USBC1") (pin "0") (pinfunction "0_0") (pintype "passive"))
    )
    (net (code "217") (name "unconnected-(USBC1-PadA5)") (class "Default")
      (node (ref "USBC1") (pin "A5") (pinfunction "A5_A5") (pintype "passive"))
    )
    (net (code "218") (name "unconnected-(USBC1-PadA8)") (class "Default")
      (node (ref "USBC1") (pin "A8") (pinfunction "A8_A8") (pintype "passive"))
    )
    (net (code "219") (name "unconnected-(USBC1-PadB5)") (class "Default")
      (node (ref "USBC1") (pin "B5") (pinfunction "B5_B5") (pintype "passive"))
    )
    (net (code "220") (name "unconnected-(USBC1-PadB8)") (class "Default")
      (node (ref "USBC1") (pin "B8") (pinfunction "B8_B8") (pintype "passive"))
    )
  )
)
